# 2716_adapter.net
KiCad netlist of a schematic drawn in EAGLE
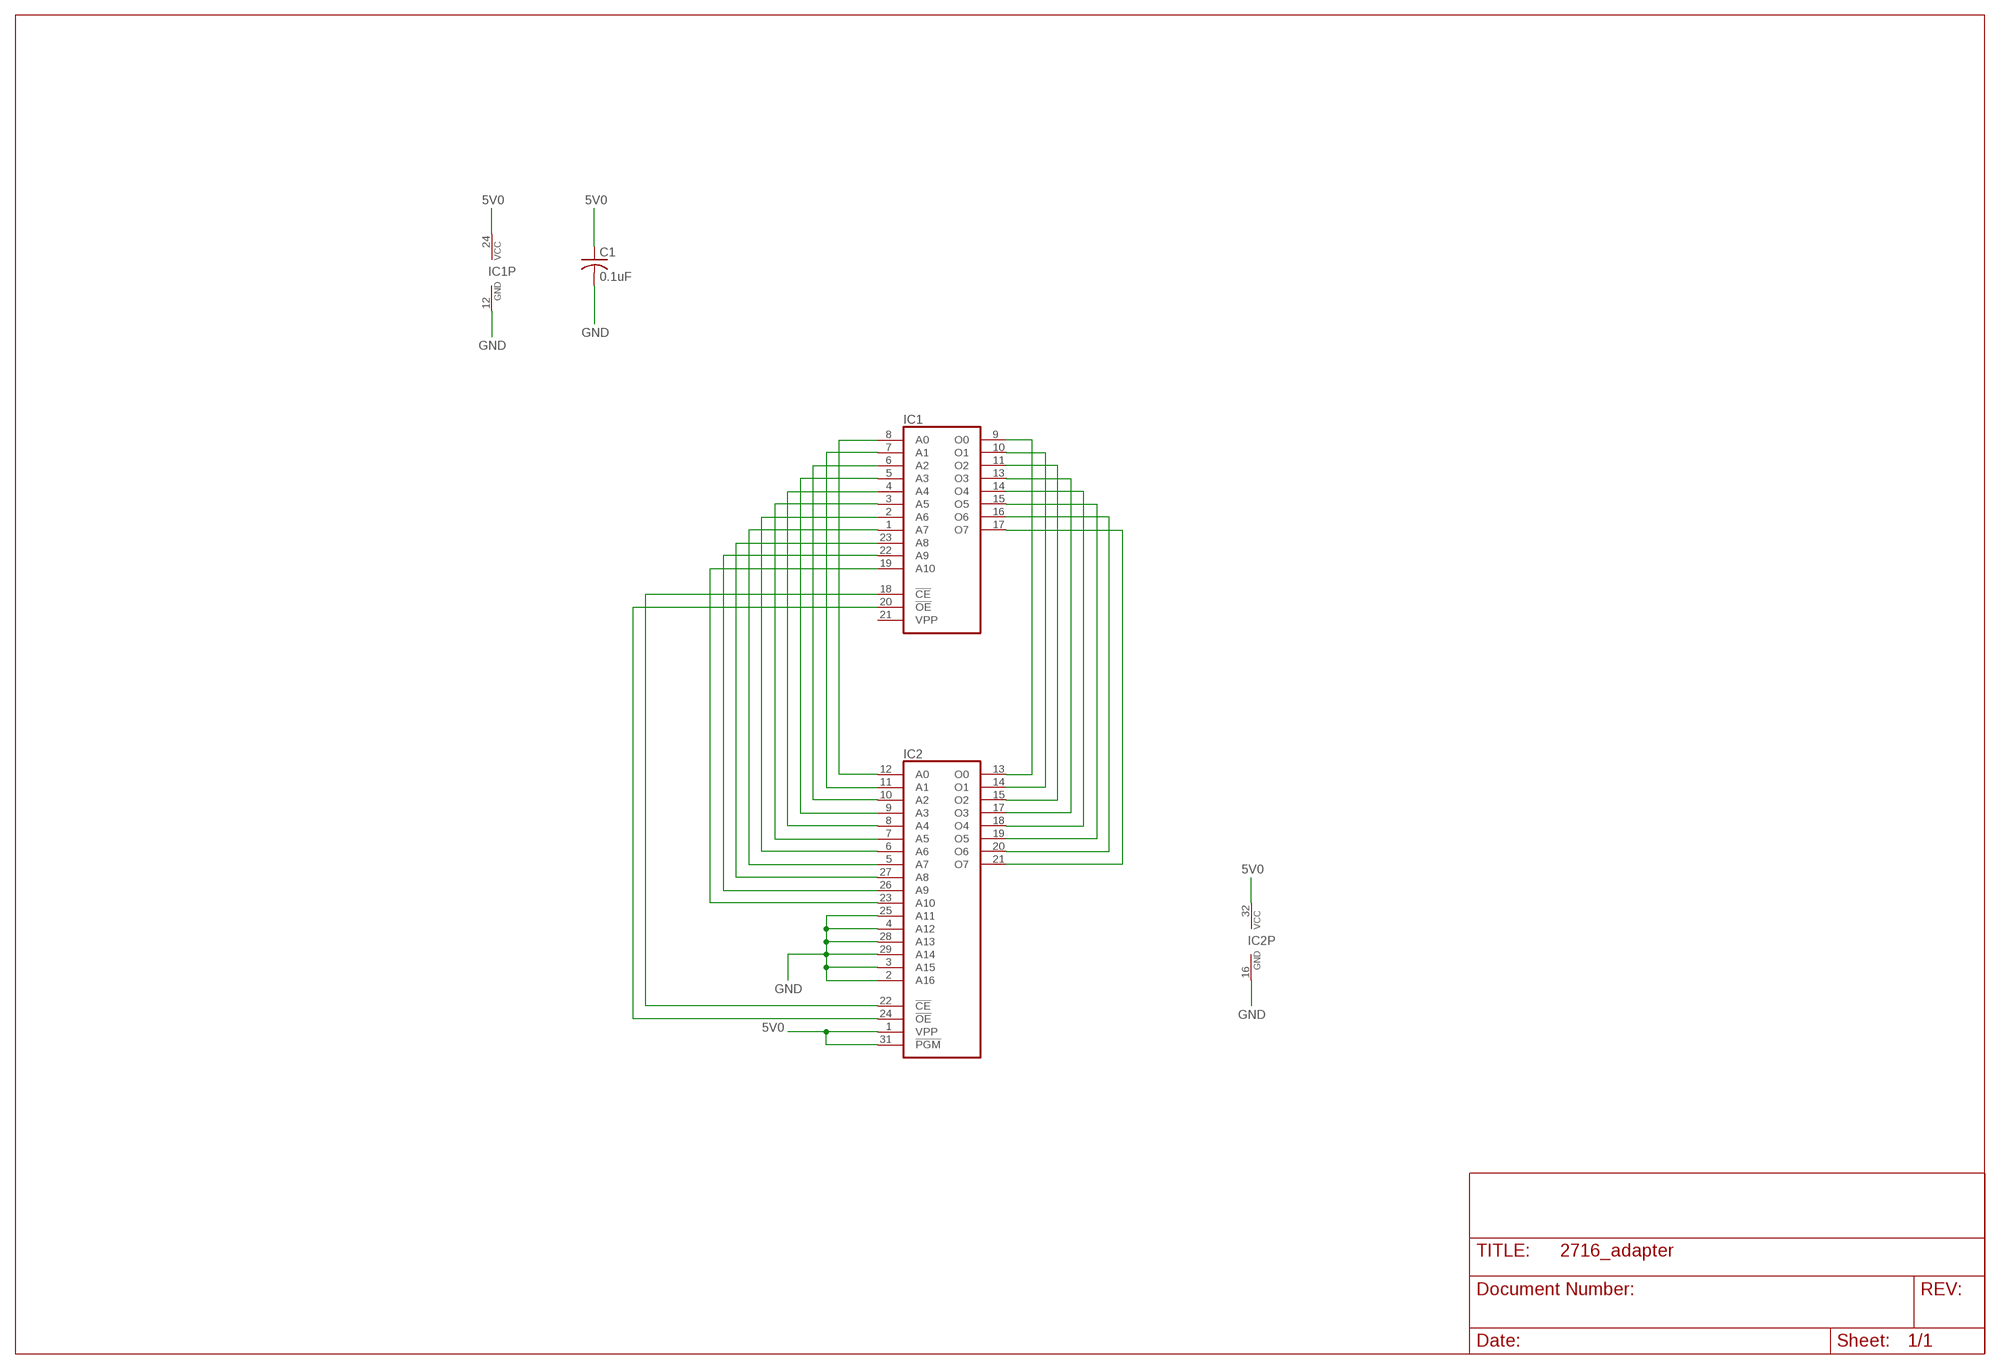
[diagram p0: schematic, sheet 1]

(export (version "E")
  (design (tool "Eeschema 10.0.6"))
  (components
    (comp (ref "C1")
      (value "0.1uF")
      (footprint "eagle-import:C0603K")
      (libsource (lib "eagle-import") (part "C-USC0603K"))
    )
    (comp (ref "IC1")
      (value "2716")
      (footprint "eagle-import:DIL24")
      (libsource (lib "eagle-import") (part "2716"))
    )
    (comp (ref "IC2")
      (value "27010PLCC32")
      (footprint "eagle-import:PLCC32R")
      (libsource (lib "eagle-import") (part "27010PLCC32"))
    )
  )
  (nets
    (net (code "1") (name "/5V0") (class "Default")
      (node (ref "C1") (pin "1") (pinfunction "1_1") (pintype "passive"))
      (node (ref "IC1") (pin "24") (pinfunction "VCC_24") (pintype "power_in"))
      (node (ref "IC2") (pin "1") (pinfunction "VPP_1") (pintype "input"))
      (node (ref "IC2") (pin "31") (pinfunction "~{PGM}_31") (pintype "input"))
      (node (ref "IC2") (pin "32") (pinfunction "VCC_32") (pintype "power_in"))
    )
    (net (code "2") (name "/GND") (class "Default")
      (node (ref "C1") (pin "2") (pinfunction "2_2") (pintype "passive"))
      (node (ref "IC1") (pin "12") (pinfunction "GND_12") (pintype "power_in"))
      (node (ref "IC2") (pin "16") (pinfunction "GND_16") (pintype "power_in"))
      (node (ref "IC2") (pin "2") (pinfunction "A16_2") (pintype "input"))
      (node (ref "IC2") (pin "25") (pinfunction "A11_25") (pintype "input"))
      (node (ref "IC2") (pin "28") (pinfunction "A13_28") (pintype "input"))
      (node (ref "IC2") (pin "29") (pinfunction "A14_29") (pintype "input"))
      (node (ref "IC2") (pin "3") (pinfunction "A15_3") (pintype "input"))
      (node (ref "IC2") (pin "4") (pinfunction "A12_4") (pintype "input"))
    )
    (net (code "3") (name "Net-(IC1A-A0)") (class "Default")
      (node (ref "IC1") (pin "8") (pinfunction "A0_8") (pintype "input"))
      (node (ref "IC2") (pin "12") (pinfunction "A0_12") (pintype "input"))
    )
    (net (code "4") (name "Net-(IC1A-A1)") (class "Default")
      (node (ref "IC1") (pin "7") (pinfunction "A1_7") (pintype "input"))
      (node (ref "IC2") (pin "11") (pinfunction "A1_11") (pintype "input"))
    )
    (net (code "5") (name "Net-(IC1A-A2)") (class "Default")
      (node (ref "IC1") (pin "6") (pinfunction "A2_6") (pintype "input"))
      (node (ref "IC2") (pin "10") (pinfunction "A2_10") (pintype "input"))
    )
    (net (code "6") (name "Net-(IC1A-A3)") (class "Default")
      (node (ref "IC1") (pin "5") (pinfunction "A3_5") (pintype "input"))
      (node (ref "IC2") (pin "9") (pinfunction "A3_9") (pintype "input"))
    )
    (net (code "7") (name "Net-(IC1A-A4)") (class "Default")
      (node (ref "IC1") (pin "4") (pinfunction "A4_4") (pintype "input"))
      (node (ref "IC2") (pin "8") (pinfunction "A4_8") (pintype "input"))
    )
    (net (code "8") (name "Net-(IC1A-A5)") (class "Default")
      (node (ref "IC1") (pin "3") (pinfunction "A5_3") (pintype "input"))
      (node (ref "IC2") (pin "7") (pinfunction "A5_7") (pintype "input"))
    )
    (net (code "9") (name "Net-(IC1A-A6)") (class "Default")
      (node (ref "IC1") (pin "2") (pinfunction "A6_2") (pintype "input"))
      (node (ref "IC2") (pin "6") (pinfunction "A6_6") (pintype "input"))
    )
    (net (code "10") (name "Net-(IC1A-A7)") (class "Default")
      (node (ref "IC1") (pin "1") (pinfunction "A7_1") (pintype "input"))
      (node (ref "IC2") (pin "5") (pinfunction "A7_5") (pintype "input"))
    )
    (net (code "11") (name "Net-(IC1A-A8)") (class "Default")
      (node (ref "IC1") (pin "23") (pinfunction "A8_23") (pintype "input"))
      (node (ref "IC2") (pin "27") (pinfunction "A8_27") (pintype "input"))
    )
    (net (code "12") (name "Net-(IC1A-A9)") (class "Default")
      (node (ref "IC1") (pin "22") (pinfunction "A9_22") (pintype "input"))
      (node (ref "IC2") (pin "26") (pinfunction "A9_26") (pintype "input"))
    )
    (net (code "13") (name "Net-(IC1A-A10)") (class "Default")
      (node (ref "IC1") (pin "19") (pinfunction "A10_19") (pintype "input"))
      (node (ref "IC2") (pin "23") (pinfunction "A10_23") (pintype "input"))
    )
    (net (code "14") (name "Net-(IC1A-O0)") (class "Default")
      (node (ref "IC1") (pin "9") (pinfunction "O0_9") (pintype "tri_state"))
      (node (ref "IC2") (pin "13") (pinfunction "O0_13") (pintype "tri_state"))
    )
    (net (code "15") (name "Net-(IC1A-O1)") (class "Default")
      (node (ref "IC1") (pin "10") (pinfunction "O1_10") (pintype "tri_state"))
      (node (ref "IC2") (pin "14") (pinfunction "O1_14") (pintype "tri_state"))
    )
    (net (code "16") (name "Net-(IC1A-O2)") (class "Default")
      (node (ref "IC1") (pin "11") (pinfunction "O2_11") (pintype "tri_state"))
      (node (ref "IC2") (pin "15") (pinfunction "O2_15") (pintype "tri_state"))
    )
    (net (code "17") (name "Net-(IC1A-O3)") (class "Default")
      (node (ref "IC1") (pin "13") (pinfunction "O3_13") (pintype "tri_state"))
      (node (ref "IC2") (pin "17") (pinfunction "O3_17") (pintype "tri_state"))
    )
    (net (code "18") (name "Net-(IC1A-O4)") (class "Default")
      (node (ref "IC1") (pin "14") (pinfunction "O4_14") (pintype "tri_state"))
      (node (ref "IC2") (pin "18") (pinfunction "O4_18") (pintype "tri_state"))
    )
    (net (code "19") (name "Net-(IC1A-O5)") (class "Default")
      (node (ref "IC1") (pin "15") (pinfunction "O5_15") (pintype "tri_state"))
      (node (ref "IC2") (pin "19") (pinfunction "O5_19") (pintype "tri_state"))
    )
    (net (code "20") (name "Net-(IC1A-O6)") (class "Default")
      (node (ref "IC1") (pin "16") (pinfunction "O6_16") (pintype "tri_state"))
      (node (ref "IC2") (pin "20") (pinfunction "O6_20") (pintype "tri_state"))
    )
    (net (code "21") (name "Net-(IC1A-O7)") (class "Default")
      (node (ref "IC1") (pin "17") (pinfunction "O7_17") (pintype "tri_state"))
      (node (ref "IC2") (pin "21") (pinfunction "O7_21") (pintype "tri_state"))
    )
    (net (code "22") (name "Net-(IC1A-~{CE})") (class "Default")
      (node (ref "IC1") (pin "18") (pinfunction "~{CE}_18") (pintype "input"))
      (node (ref "IC2") (pin "22") (pinfunction "~{CE}_22") (pintype "input"))
    )
    (net (code "23") (name "Net-(IC1A-~{OE})") (class "Default")
      (node (ref "IC1") (pin "20") (pinfunction "~{OE}_20") (pintype "input"))
      (node (ref "IC2") (pin "24") (pinfunction "~{OE}_24") (pintype "input"))
    )
    (net (code "24") (name "unconnected-(IC1A-VPP-Pad21)") (class "Default")
      (node (ref "IC1") (pin "21") (pinfunction "VPP_21") (pintype "input"))
    )
  )
)
